# dc26_maneki-neko_badge_standalone_201807.net
KiCad netlist of a schematic drawn in EAGLE
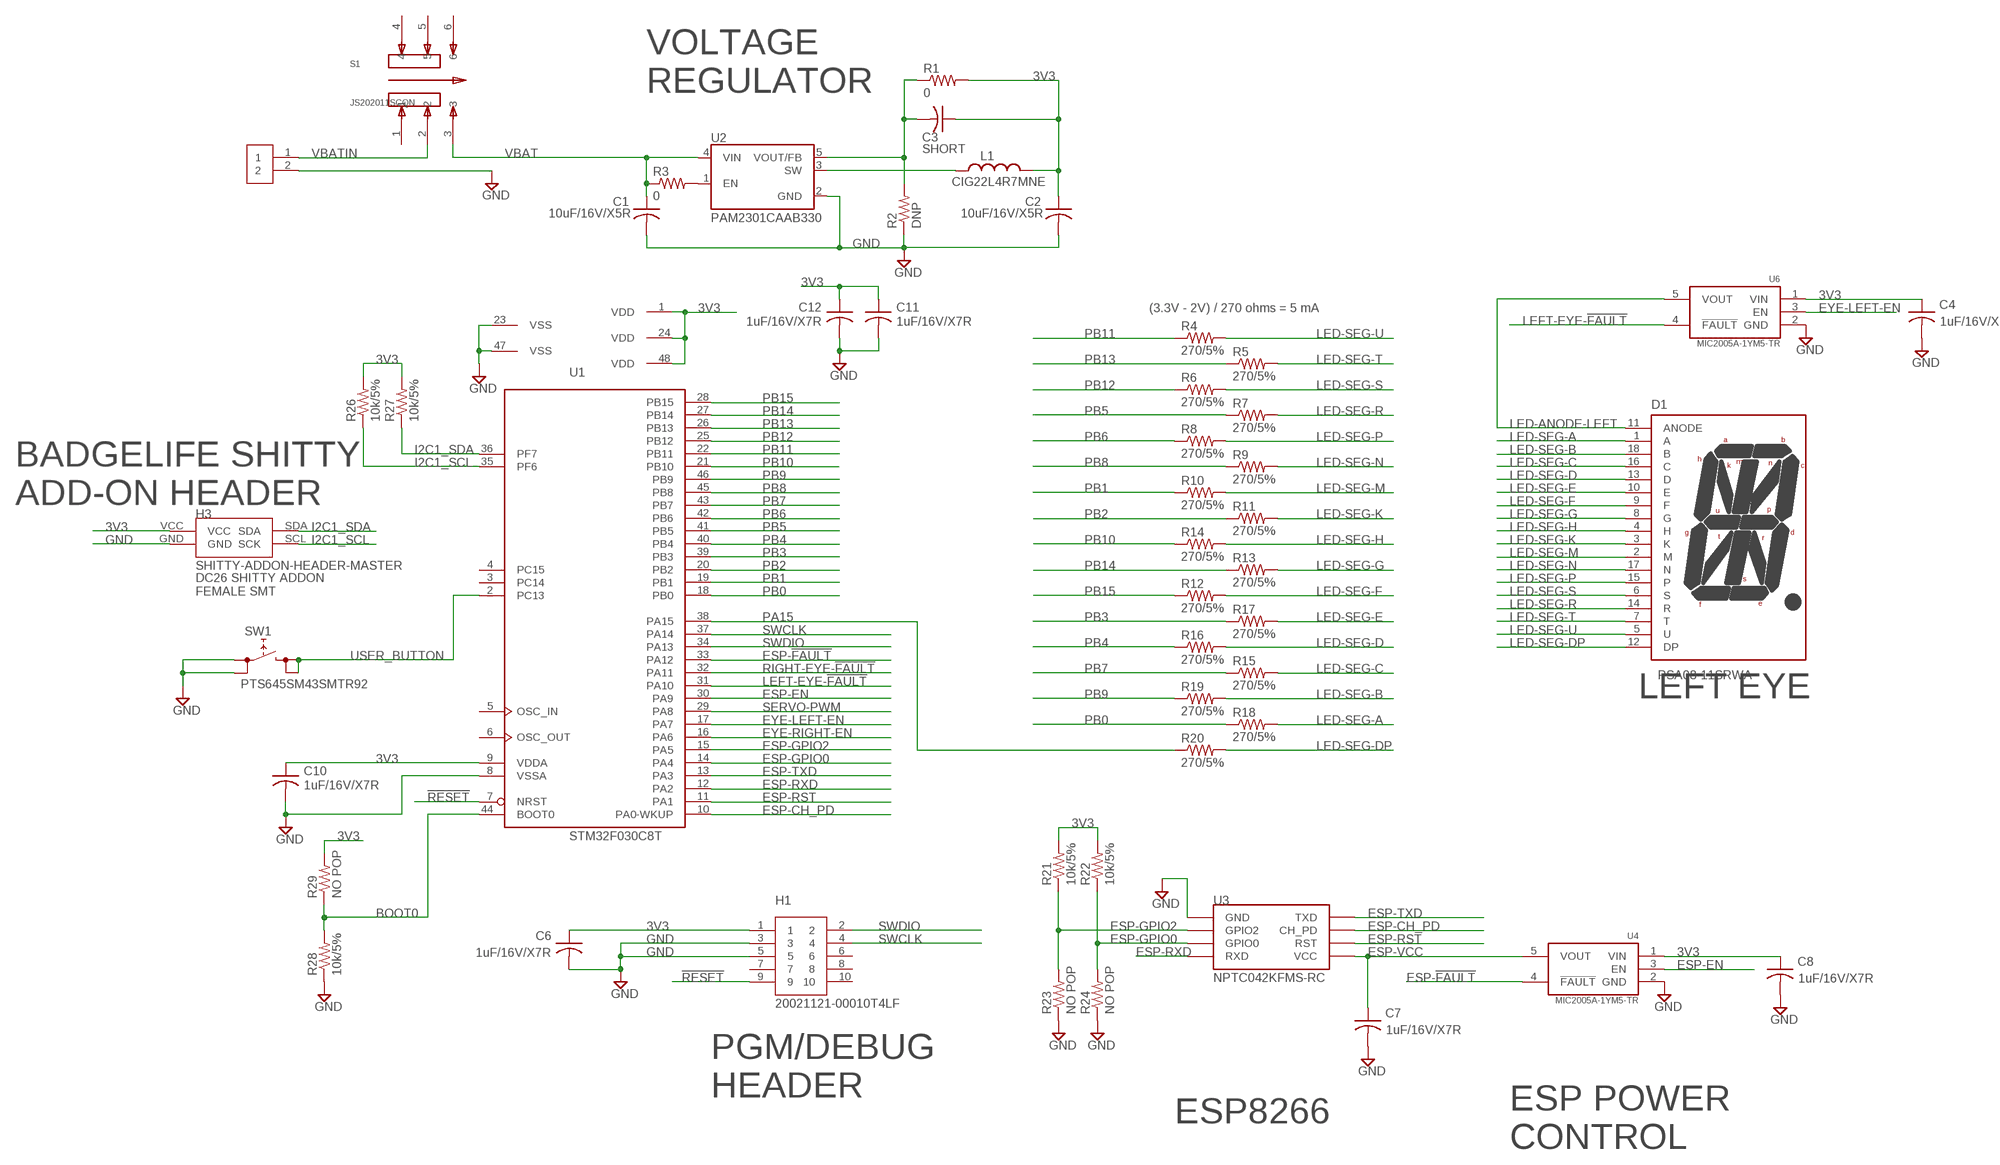
[diagram p0: schematic, sheet 1, part 1 of 2]
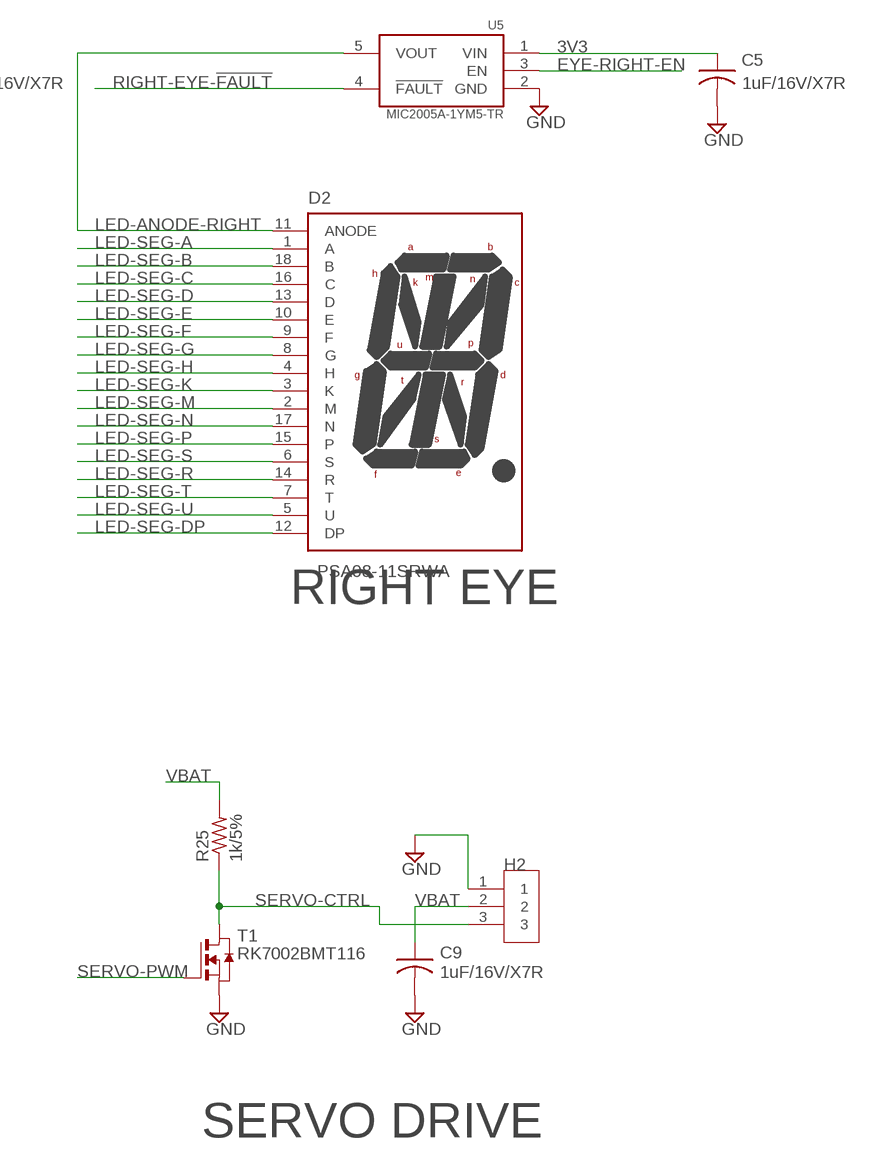
[diagram p1: schematic, sheet 1, part 2 of 2]

(export (version "E")
  (design (tool "Eeschema 10.0.6"))
  (components
    (comp (ref "C1")
      (value "10uF/16V/X5R")
      (footprint "eagle-import:C0805")
      (libsource (lib "eagle-import") (part "C-USC0805"))
    )
    (comp (ref "C2")
      (value "10uF/16V/X5R")
      (footprint "eagle-import:C0805")
      (libsource (lib "eagle-import") (part "C-USC0805"))
    )
    (comp (ref "C3")
      (value "SHORT")
      (footprint "eagle-import:C0805")
      (libsource (lib "eagle-import") (part "C-USC0805"))
    )
    (comp (ref "C4")
      (value "1uF/16V/X7R")
      (footprint "eagle-import:C0805")
      (libsource (lib "eagle-import") (part "C-USC0805"))
    )
    (comp (ref "C5")
      (value "1uF/16V/X7R")
      (footprint "eagle-import:C0805")
      (libsource (lib "eagle-import") (part "C-USC0805"))
    )
    (comp (ref "C6")
      (value "1uF/16V/X7R")
      (footprint "eagle-import:C0805")
      (libsource (lib "eagle-import") (part "C-USC0805"))
    )
    (comp (ref "C7")
      (value "1uF/16V/X7R")
      (footprint "eagle-import:C0805")
      (libsource (lib "eagle-import") (part "C-USC0805"))
    )
    (comp (ref "C8")
      (value "1uF/16V/X7R")
      (footprint "eagle-import:C0805")
      (libsource (lib "eagle-import") (part "C-USC0805"))
    )
    (comp (ref "C9")
      (value "1uF/16V/X7R")
      (footprint "eagle-import:C0805")
      (libsource (lib "eagle-import") (part "C-USC0805"))
    )
    (comp (ref "C10")
      (value "1uF/16V/X7R")
      (footprint "eagle-import:C0805")
      (libsource (lib "eagle-import") (part "C-USC0805"))
    )
    (comp (ref "C11")
      (value "1uF/16V/X7R")
      (footprint "eagle-import:C0805")
      (libsource (lib "eagle-import") (part "C-USC0805"))
    )
    (comp (ref "C12")
      (value "1uF/16V/X7R")
      (footprint "eagle-import:C0805")
      (libsource (lib "eagle-import") (part "C-USC0805"))
    )
    (comp (ref "D1")
      (value "PSA08-11SRWA")
      (footprint "eagle-import:PSA08-11SRWA")
      (libsource (lib "eagle-import") (part "PSA08-11SRWA"))
    )
    (comp (ref "D2")
      (value "PSA08-11SRWA")
      (footprint "eagle-import:PSA08-11SRWA")
      (libsource (lib "eagle-import") (part "PSA08-11SRWA"))
    )
    (comp (ref "H1")
      (value "20021121-00010T4LF")
      (footprint "eagle-import:20021121-00010T4LF")
      (libsource (lib "eagle-import") (part "20021121-00010T4LF"))
    )
    (comp (ref "H2")
      (value "M20-8890345R")
      (footprint "eagle-import:M20-8890345R")
      (libsource (lib "eagle-import") (part "M20-8890345R"))
    )
    (comp (ref "H3")
      (value "SHITTY-ADDON-HEADER-MASTER")
      (footprint "eagle-import:2X2-0.1INCH-FEMALE-SMT")
      (libsource (lib "eagle-import") (part "SHITTY-ADDON-HEADER-MASTER"))
    )
    (comp (ref "L1")
      (value "CIG22L4R7MNE")
      (footprint "eagle-import:L-1008-US")
      (libsource (lib "eagle-import") (part "CIG22L4R7MNE"))
    )
    (comp (ref "R1")
      (value "0")
      (footprint "eagle-import:R0805")
      (libsource (lib "eagle-import") (part "R-US_R0805"))
    )
    (comp (ref "R2")
      (value "DNP")
      (footprint "eagle-import:R0805")
      (libsource (lib "eagle-import") (part "R-US_R0805"))
    )
    (comp (ref "R3")
      (value "0")
      (footprint "eagle-import:R0805")
      (libsource (lib "eagle-import") (part "R-US_R0805"))
    )
    (comp (ref "R4")
      (value "270/5%")
      (footprint "eagle-import:R0805")
      (libsource (lib "eagle-import") (part "R-US_R0805"))
    )
    (comp (ref "R5")
      (value "270/5%")
      (footprint "eagle-import:R0805")
      (libsource (lib "eagle-import") (part "R-US_R0805"))
    )
    (comp (ref "R6")
      (value "270/5%")
      (footprint "eagle-import:R0805")
      (libsource (lib "eagle-import") (part "R-US_R0805"))
    )
    (comp (ref "R7")
      (value "270/5%")
      (footprint "eagle-import:R0805")
      (libsource (lib "eagle-import") (part "R-US_R0805"))
    )
    (comp (ref "R8")
      (value "270/5%")
      (footprint "eagle-import:R0805")
      (libsource (lib "eagle-import") (part "R-US_R0805"))
    )
    (comp (ref "R9")
      (value "270/5%")
      (footprint "eagle-import:R0805")
      (libsource (lib "eagle-import") (part "R-US_R0805"))
    )
    (comp (ref "R10")
      (value "270/5%")
      (footprint "eagle-import:R0805")
      (libsource (lib "eagle-import") (part "R-US_R0805"))
    )
    (comp (ref "R11")
      (value "270/5%")
      (footprint "eagle-import:R0805")
      (libsource (lib "eagle-import") (part "R-US_R0805"))
    )
    (comp (ref "R12")
      (value "270/5%")
      (footprint "eagle-import:R0805")
      (libsource (lib "eagle-import") (part "R-US_R0805"))
    )
    (comp (ref "R13")
      (value "270/5%")
      (footprint "eagle-import:R0805")
      (libsource (lib "eagle-import") (part "R-US_R0805"))
    )
    (comp (ref "R14")
      (value "270/5%")
      (footprint "eagle-import:R0805")
      (libsource (lib "eagle-import") (part "R-US_R0805"))
    )
    (comp (ref "R15")
      (value "270/5%")
      (footprint "eagle-import:R0805")
      (libsource (lib "eagle-import") (part "R-US_R0805"))
    )
    (comp (ref "R16")
      (value "270/5%")
      (footprint "eagle-import:R0805")
      (libsource (lib "eagle-import") (part "R-US_R0805"))
    )
    (comp (ref "R17")
      (value "270/5%")
      (footprint "eagle-import:R0805")
      (libsource (lib "eagle-import") (part "R-US_R0805"))
    )
    (comp (ref "R18")
      (value "270/5%")
      (footprint "eagle-import:R0805")
      (libsource (lib "eagle-import") (part "R-US_R0805"))
    )
    (comp (ref "R19")
      (value "270/5%")
      (footprint "eagle-import:R0805")
      (libsource (lib "eagle-import") (part "R-US_R0805"))
    )
    (comp (ref "R20")
      (value "270/5%")
      (footprint "eagle-import:R0805")
      (libsource (lib "eagle-import") (part "R-US_R0805"))
    )
    (comp (ref "R21")
      (value "10k/5%")
      (footprint "eagle-import:R0805")
      (libsource (lib "eagle-import") (part "R-US_R0805"))
    )
    (comp (ref "R22")
      (value "10k/5%")
      (footprint "eagle-import:R0805")
      (libsource (lib "eagle-import") (part "R-US_R0805"))
    )
    (comp (ref "R23")
      (value "NO POP")
      (footprint "eagle-import:R0805")
      (libsource (lib "eagle-import") (part "R-US_R0805"))
    )
    (comp (ref "R24")
      (value "NO POP")
      (footprint "eagle-import:R0805")
      (libsource (lib "eagle-import") (part "R-US_R0805"))
    )
    (comp (ref "R25")
      (value "1k/5%")
      (footprint "eagle-import:R0805")
      (libsource (lib "eagle-import") (part "R-US_R0805"))
    )
    (comp (ref "R26")
      (value "10k/5%")
      (footprint "eagle-import:R0805")
      (libsource (lib "eagle-import") (part "R-US_R0805"))
    )
    (comp (ref "R27")
      (value "10k/5%")
      (footprint "eagle-import:R0805")
      (libsource (lib "eagle-import") (part "R-US_R0805"))
    )
    (comp (ref "R28")
      (value "10k/5%")
      (footprint "eagle-import:R0805")
      (libsource (lib "eagle-import") (part "R-US_R0805"))
    )
    (comp (ref "R29")
      (value "NO POP")
      (footprint "eagle-import:R0805")
      (libsource (lib "eagle-import") (part "R-US_R0805"))
    )
    (comp (ref "S1")
      (value "JS202011SCQN")
      (footprint "eagle-import:SW_JS202011SCQN")
      (fields (field (name "MF") "C&K Components"))
      (libsource (lib "eagle-import") (part "JS202011SCQN"))
    )
    (comp (ref "SW1")
      (value "PTS645SM43SMTR92")
      (footprint "eagle-import:PTS645SM43SMTR92")
      (libsource (lib "eagle-import") (part "PTS645SM43SMTR92"))
    )
    (comp (ref "T1")
      (value "RK7002BMT116")
      (footprint "eagle-import:SOT-23")
      (libsource (lib "eagle-import") (part "NMOSSOT23"))
    )
    (comp (ref "U$2")
      (value "BATTPADS-SMT")
      (footprint "eagle-import:BATTPADS-SMT")
      (libsource (lib "eagle-import") (part "BATTPADS-SMT"))
    )
    (comp (ref "U1")
      (value "STM32F030C8T")
      (footprint "eagle-import:LQFP48")
      (libsource (lib "eagle-import") (part "STM32F030CT8"))
    )
    (comp (ref "U2")
      (value "PAM2301CAAB330")
      (footprint "eagle-import:SOT95P280X100-5N")
      (libsource (lib "eagle-import") (part "PAM2301CAAB330"))
    )
    (comp (ref "U3")
      (value "NPTC042KFMS-RC")
      (footprint "eagle-import:NPTC042KFMS-RC")
      (libsource (lib "eagle-import") (part "NPTC042KFMS-RC"))
    )
    (comp (ref "U4")
      (value "MIC2005A-1YM5-TR")
      (footprint "eagle-import:SOT95P270X145-5N")
      (libsource (lib "eagle-import") (part "MIC2005A-1YM5-TR"))
    )
    (comp (ref "U5")
      (value "MIC2005A-1YM5-TR")
      (footprint "eagle-import:SOT95P270X145-5N")
      (libsource (lib "eagle-import") (part "MIC2005A-1YM5-TR"))
    )
    (comp (ref "U6")
      (value "MIC2005A-1YM5-TR")
      (footprint "eagle-import:SOT95P270X145-5N")
      (libsource (lib "eagle-import") (part "MIC2005A-1YM5-TR"))
    )
  )
  (nets
    (net (code "1") (name "/3V3") (class "Default")
      (node (ref "C10") (pin "1") (pinfunction "1_1") (pintype "passive"))
      (node (ref "C11") (pin "1") (pinfunction "1_1") (pintype "passive"))
      (node (ref "C12") (pin "1") (pinfunction "1_1") (pintype "passive"))
      (node (ref "C2") (pin "1") (pinfunction "1_1") (pintype "passive"))
      (node (ref "C3") (pin "1") (pinfunction "1_1") (pintype "passive"))
      (node (ref "C4") (pin "1") (pinfunction "1_1") (pintype "passive"))
      (node (ref "C5") (pin "1") (pinfunction "1_1") (pintype "passive"))
      (node (ref "C6") (pin "1") (pinfunction "1_1") (pintype "passive"))
      (node (ref "C8") (pin "1") (pinfunction "1_1") (pintype "passive"))
      (node (ref "H1") (pin "1") (pinfunction "1_1") (pintype "bidirectional"))
      (node (ref "H3") (pin "VCC") (pinfunction "VCC_VCC") (pintype "bidirectional"))
      (node (ref "L1") (pin "P$2") (pinfunction "2_P$2") (pintype "passive"))
      (node (ref "R1") (pin "2") (pinfunction "2_2") (pintype "passive"))
      (node (ref "R21") (pin "2") (pinfunction "2_2") (pintype "passive"))
      (node (ref "R22") (pin "2") (pinfunction "2_2") (pintype "passive"))
      (node (ref "R26") (pin "2") (pinfunction "2_2") (pintype "passive"))
      (node (ref "R27") (pin "2") (pinfunction "2_2") (pintype "passive"))
      (node (ref "R29") (pin "2") (pinfunction "2_2") (pintype "passive"))
      (node (ref "U1") (pin "1") (pinfunction "VDD_1") (pintype "power_in"))
      (node (ref "U1") (pin "24") (pinfunction "VDD_24") (pintype "power_in"))
      (node (ref "U1") (pin "48") (pinfunction "VDD_48") (pintype "power_in"))
      (node (ref "U1") (pin "9") (pinfunction "VDDA_9") (pintype "power_in"))
      (node (ref "U4") (pin "1") (pinfunction "VIN_1") (pintype "bidirectional"))
      (node (ref "U5") (pin "1") (pinfunction "VIN_1") (pintype "bidirectional"))
      (node (ref "U6") (pin "1") (pinfunction "VIN_1") (pintype "bidirectional"))
    )
    (net (code "2") (name "/BOOT0") (class "Default")
      (node (ref "R28") (pin "2") (pinfunction "2_2") (pintype "passive"))
      (node (ref "R29") (pin "1") (pinfunction "1_1") (pintype "passive"))
      (node (ref "U1") (pin "44") (pinfunction "BOOT0_44") (pintype "input"))
    )
    (net (code "3") (name "/ESP-CH_PD") (class "Default")
      (node (ref "U1") (pin "10") (pinfunction "PA0-WKUP_10") (pintype "bidirectional"))
      (node (ref "U3") (pin "3") (pinfunction "CH_PD_3") (pintype "bidirectional"))
    )
    (net (code "4") (name "/ESP-EN") (class "Default")
      (node (ref "U1") (pin "30") (pinfunction "PA9_30") (pintype "bidirectional"))
      (node (ref "U4") (pin "3") (pinfunction "EN_3") (pintype "bidirectional"))
    )
    (net (code "5") (name "/ESP-GPIO0") (class "Default")
      (node (ref "R22") (pin "1") (pinfunction "1_1") (pintype "passive"))
      (node (ref "R24") (pin "2") (pinfunction "2_2") (pintype "passive"))
      (node (ref "U1") (pin "14") (pinfunction "PA4_14") (pintype "bidirectional"))
      (node (ref "U3") (pin "6") (pinfunction "GPIO0_6") (pintype "bidirectional"))
    )
    (net (code "6") (name "/ESP-GPIO2") (class "Default")
      (node (ref "R21") (pin "1") (pinfunction "1_1") (pintype "passive"))
      (node (ref "R23") (pin "2") (pinfunction "2_2") (pintype "passive"))
      (node (ref "U1") (pin "15") (pinfunction "PA5_15") (pintype "bidirectional"))
      (node (ref "U3") (pin "4") (pinfunction "GPIO2_4") (pintype "bidirectional"))
    )
    (net (code "7") (name "/ESP-RST") (class "Default")
      (node (ref "U1") (pin "11") (pinfunction "PA1_11") (pintype "bidirectional"))
      (node (ref "U3") (pin "5") (pinfunction "RST_5") (pintype "bidirectional"))
    )
    (net (code "8") (name "/ESP-RXD") (class "Default")
      (node (ref "U1") (pin "12") (pinfunction "PA2_12") (pintype "bidirectional"))
      (node (ref "U3") (pin "8") (pinfunction "RXD_8") (pintype "bidirectional"))
    )
    (net (code "9") (name "/ESP-TXD") (class "Default")
      (node (ref "U1") (pin "13") (pinfunction "PA3_13") (pintype "bidirectional"))
      (node (ref "U3") (pin "1") (pinfunction "TXD_1") (pintype "bidirectional"))
    )
    (net (code "10") (name "/ESP-VCC") (class "Default")
      (node (ref "C7") (pin "1") (pinfunction "1_1") (pintype "passive"))
      (node (ref "U3") (pin "7") (pinfunction "VCC_7") (pintype "bidirectional"))
      (node (ref "U4") (pin "5") (pinfunction "VOUT_5") (pintype "bidirectional"))
    )
    (net (code "11") (name "/ESP-~{FAULT}") (class "Default")
      (node (ref "U1") (pin "33") (pinfunction "PA12_33") (pintype "bidirectional"))
      (node (ref "U4") (pin "4") (pinfunction "~{FAULT}_4") (pintype "bidirectional"))
    )
    (net (code "12") (name "/EYE-LEFT-EN") (class "Default")
      (node (ref "U1") (pin "17") (pinfunction "PA7_17") (pintype "bidirectional"))
      (node (ref "U6") (pin "3") (pinfunction "EN_3") (pintype "bidirectional"))
    )
    (net (code "13") (name "/EYE-RIGHT-EN") (class "Default")
      (node (ref "U1") (pin "16") (pinfunction "PA6_16") (pintype "bidirectional"))
      (node (ref "U5") (pin "3") (pinfunction "EN_3") (pintype "bidirectional"))
    )
    (net (code "14") (name "/I2C1_SCL") (class "Default")
      (node (ref "H3") (pin "SCL") (pinfunction "SCK_SCL") (pintype "bidirectional"))
      (node (ref "R26") (pin "1") (pinfunction "1_1") (pintype "passive"))
      (node (ref "U1") (pin "35") (pinfunction "PF6_35") (pintype "bidirectional"))
    )
    (net (code "15") (name "/I2C1_SDA") (class "Default")
      (node (ref "H3") (pin "SDA") (pinfunction "SDA_SDA") (pintype "bidirectional"))
      (node (ref "R27") (pin "1") (pinfunction "1_1") (pintype "passive"))
      (node (ref "U1") (pin "36") (pinfunction "PF7_36") (pintype "bidirectional"))
    )
    (net (code "16") (name "/LED-ANODE-LEFT") (class "Default")
      (node (ref "D1") (pin "11") (pinfunction "ANODE_11") (pintype "bidirectional"))
      (node (ref "U6") (pin "5") (pinfunction "VOUT_5") (pintype "bidirectional"))
    )
    (net (code "17") (name "/LED-ANODE-RIGHT") (class "Default")
      (node (ref "D2") (pin "11") (pinfunction "ANODE_11") (pintype "bidirectional"))
      (node (ref "U5") (pin "5") (pinfunction "VOUT_5") (pintype "bidirectional"))
    )
    (net (code "18") (name "/LED-SEG-A") (class "Default")
      (node (ref "D1") (pin "1") (pinfunction "A_1") (pintype "bidirectional"))
      (node (ref "D2") (pin "1") (pinfunction "A_1") (pintype "bidirectional"))
      (node (ref "R18") (pin "2") (pinfunction "2_2") (pintype "passive"))
    )
    (net (code "19") (name "/LED-SEG-B") (class "Default")
      (node (ref "D1") (pin "18") (pinfunction "B_18") (pintype "bidirectional"))
      (node (ref "D2") (pin "18") (pinfunction "B_18") (pintype "bidirectional"))
      (node (ref "R19") (pin "2") (pinfunction "2_2") (pintype "passive"))
    )
    (net (code "20") (name "/LED-SEG-C") (class "Default")
      (node (ref "D1") (pin "16") (pinfunction "C_16") (pintype "bidirectional"))
      (node (ref "D2") (pin "16") (pinfunction "C_16") (pintype "bidirectional"))
      (node (ref "R15") (pin "2") (pinfunction "2_2") (pintype "passive"))
    )
    (net (code "21") (name "/LED-SEG-D") (class "Default")
      (node (ref "D1") (pin "13") (pinfunction "D_13") (pintype "bidirectional"))
      (node (ref "D2") (pin "13") (pinfunction "D_13") (pintype "bidirectional"))
      (node (ref "R16") (pin "2") (pinfunction "2_2") (pintype "passive"))
    )
    (net (code "22") (name "/LED-SEG-DP") (class "Default")
      (node (ref "D1") (pin "12") (pinfunction "DP_12") (pintype "bidirectional"))
      (node (ref "D2") (pin "12") (pinfunction "DP_12") (pintype "bidirectional"))
      (node (ref "R20") (pin "2") (pinfunction "2_2") (pintype "passive"))
    )
    (net (code "23") (name "/LED-SEG-E") (class "Default")
      (node (ref "D1") (pin "10") (pinfunction "E_10") (pintype "bidirectional"))
      (node (ref "D2") (pin "10") (pinfunction "E_10") (pintype "bidirectional"))
      (node (ref "R17") (pin "2") (pinfunction "2_2") (pintype "passive"))
    )
    (net (code "24") (name "/LED-SEG-F") (class "Default")
      (node (ref "D1") (pin "9") (pinfunction "F_9") (pintype "bidirectional"))
      (node (ref "D2") (pin "9") (pinfunction "F_9") (pintype "bidirectional"))
      (node (ref "R12") (pin "2") (pinfunction "2_2") (pintype "passive"))
    )
    (net (code "25") (name "/LED-SEG-G") (class "Default")
      (node (ref "D1") (pin "8") (pinfunction "G_8") (pintype "bidirectional"))
      (node (ref "D2") (pin "8") (pinfunction "G_8") (pintype "bidirectional"))
      (node (ref "R13") (pin "2") (pinfunction "2_2") (pintype "passive"))
    )
    (net (code "26") (name "/LED-SEG-H") (class "Default")
      (node (ref "D1") (pin "4") (pinfunction "H_4") (pintype "bidirectional"))
      (node (ref "D2") (pin "4") (pinfunction "H_4") (pintype "bidirectional"))
      (node (ref "R14") (pin "2") (pinfunction "2_2") (pintype "passive"))
    )
    (net (code "27") (name "/LED-SEG-K") (class "Default")
      (node (ref "D1") (pin "3") (pinfunction "K_3") (pintype "bidirectional"))
      (node (ref "D2") (pin "3") (pinfunction "K_3") (pintype "bidirectional"))
      (node (ref "R11") (pin "2") (pinfunction "2_2") (pintype "passive"))
    )
    (net (code "28") (name "/LED-SEG-M") (class "Default")
      (node (ref "D1") (pin "2") (pinfunction "M_2") (pintype "bidirectional"))
      (node (ref "D2") (pin "2") (pinfunction "M_2") (pintype "bidirectional"))
      (node (ref "R10") (pin "2") (pinfunction "2_2") (pintype "passive"))
    )
    (net (code "29") (name "/LED-SEG-N") (class "Default")
      (node (ref "D1") (pin "17") (pinfunction "N_17") (pintype "bidirectional"))
      (node (ref "D2") (pin "17") (pinfunction "N_17") (pintype "bidirectional"))
      (node (ref "R9") (pin "2") (pinfunction "2_2") (pintype "passive"))
    )
    (net (code "30") (name "/LED-SEG-P") (class "Default")
      (node (ref "D1") (pin "15") (pinfunction "P_15") (pintype "bidirectional"))
      (node (ref "D2") (pin "15") (pinfunction "P_15") (pintype "bidirectional"))
      (node (ref "R8") (pin "2") (pinfunction "2_2") (pintype "passive"))
    )
    (net (code "31") (name "/LED-SEG-R") (class "Default")
      (node (ref "D1") (pin "14") (pinfunction "R_14") (pintype "bidirectional"))
      (node (ref "D2") (pin "14") (pinfunction "R_14") (pintype "bidirectional"))
      (node (ref "R7") (pin "2") (pinfunction "2_2") (pintype "passive"))
    )
    (net (code "32") (name "/LED-SEG-S") (class "Default")
      (node (ref "D1") (pin "6") (pinfunction "S_6") (pintype "bidirectional"))
      (node (ref "D2") (pin "6") (pinfunction "S_6") (pintype "bidirectional"))
      (node (ref "R6") (pin "2") (pinfunction "2_2") (pintype "passive"))
    )
    (net (code "33") (name "/LED-SEG-T") (class "Default")
      (node (ref "D1") (pin "7") (pinfunction "T_7") (pintype "bidirectional"))
      (node (ref "D2") (pin "7") (pinfunction "T_7") (pintype "bidirectional"))
      (node (ref "R5") (pin "2") (pinfunction "2_2") (pintype "passive"))
    )
    (net (code "34") (name "/LED-SEG-U") (class "Default")
      (node (ref "D1") (pin "5") (pinfunction "U_5") (pintype "bidirectional"))
      (node (ref "D2") (pin "5") (pinfunction "U_5") (pintype "bidirectional"))
      (node (ref "R4") (pin "2") (pinfunction "2_2") (pintype "passive"))
    )
    (net (code "35") (name "/LEFT-EYE-~{FAULT}") (class "Default")
      (node (ref "U1") (pin "31") (pinfunction "PA10_31") (pintype "bidirectional"))
      (node (ref "U6") (pin "4") (pinfunction "~{FAULT}_4") (pintype "bidirectional"))
    )
    (net (code "36") (name "/PA15") (class "Default")
      (node (ref "R20") (pin "1") (pinfunction "1_1") (pintype "passive"))
      (node (ref "U1") (pin "38") (pinfunction "PA15_38") (pintype "bidirectional"))
    )
    (net (code "37") (name "/PB0") (class "Default")
      (node (ref "R18") (pin "1") (pinfunction "1_1") (pintype "passive"))
      (node (ref "U1") (pin "18") (pinfunction "PB0_18") (pintype "bidirectional"))
    )
    (net (code "38") (name "/PB1") (class "Default")
      (node (ref "R10") (pin "1") (pinfunction "1_1") (pintype "passive"))
      (node (ref "U1") (pin "19") (pinfunction "PB1_19") (pintype "bidirectional"))
    )
    (net (code "39") (name "/PB2") (class "Default")
      (node (ref "R11") (pin "1") (pinfunction "1_1") (pintype "passive"))
      (node (ref "U1") (pin "20") (pinfunction "PB2_20") (pintype "bidirectional"))
    )
    (net (code "40") (name "/PB3") (class "Default")
      (node (ref "R17") (pin "1") (pinfunction "1_1") (pintype "passive"))
      (node (ref "U1") (pin "39") (pinfunction "PB3_39") (pintype "bidirectional"))
    )
    (net (code "41") (name "/PB4") (class "Default")
      (node (ref "R16") (pin "1") (pinfunction "1_1") (pintype "passive"))
      (node (ref "U1") (pin "40") (pinfunction "PB4_40") (pintype "bidirectional"))
    )
    (net (code "42") (name "/PB5") (class "Default")
      (node (ref "R7") (pin "1") (pinfunction "1_1") (pintype "passive"))
      (node (ref "U1") (pin "41") (pinfunction "PB5_41") (pintype "bidirectional"))
    )
    (net (code "43") (name "/PB6") (class "Default")
      (node (ref "R8") (pin "1") (pinfunction "1_1") (pintype "passive"))
      (node (ref "U1") (pin "42") (pinfunction "PB6_42") (pintype "bidirectional"))
    )
    (net (code "44") (name "/PB7") (class "Default")
      (node (ref "R15") (pin "1") (pinfunction "1_1") (pintype "passive"))
      (node (ref "U1") (pin "43") (pinfunction "PB7_43") (pintype "bidirectional"))
    )
    (net (code "45") (name "/PB8") (class "Default")
      (node (ref "R9") (pin "1") (pinfunction "1_1") (pintype "passive"))
      (node (ref "U1") (pin "45") (pinfunction "PB8_45") (pintype "bidirectional"))
    )
    (net (code "46") (name "/PB9") (class "Default")
      (node (ref "R19") (pin "1") (pinfunction "1_1") (pintype "passive"))
      (node (ref "U1") (pin "46") (pinfunction "PB9_46") (pintype "bidirectional"))
    )
    (net (code "47") (name "/PB10") (class "Default")
      (node (ref "R14") (pin "1") (pinfunction "1_1") (pintype "passive"))
      (node (ref "U1") (pin "21") (pinfunction "PB10_21") (pintype "bidirectional"))
    )
    (net (code "48") (name "/PB11") (class "Default")
      (node (ref "R4") (pin "1") (pinfunction "1_1") (pintype "passive"))
      (node (ref "U1") (pin "22") (pinfunction "PB11_22") (pintype "bidirectional"))
    )
    (net (code "49") (name "/PB12") (class "Default")
      (node (ref "R6") (pin "1") (pinfunction "1_1") (pintype "passive"))
      (node (ref "U1") (pin "25") (pinfunction "PB12_25") (pintype "bidirectional"))
    )
    (net (code "50") (name "/PB13") (class "Default")
      (node (ref "R5") (pin "1") (pinfunction "1_1") (pintype "passive"))
      (node (ref "U1") (pin "26") (pinfunction "PB13_26") (pintype "bidirectional"))
    )
    (net (code "51") (name "/PB14") (class "Default")
      (node (ref "R13") (pin "1") (pinfunction "1_1") (pintype "passive"))
      (node (ref "U1") (pin "27") (pinfunction "PB14_27") (pintype "bidirectional"))
    )
    (net (code "52") (name "/PB15") (class "Default")
      (node (ref "R12") (pin "1") (pinfunction "1_1") (pintype "passive"))
      (node (ref "U1") (pin "28") (pinfunction "PB15_28") (pintype "bidirectional"))
    )
    (net (code "53") (name "/RIGHT-EYE-~{FAULT}") (class "Default")
      (node (ref "U1") (pin "32") (pinfunction "PA11_32") (pintype "bidirectional"))
      (node (ref "U5") (pin "4") (pinfunction "~{FAULT}_4") (pintype "bidirectional"))
    )
    (net (code "54") (name "/SERVO-CTRL") (class "Default")
      (node (ref "H2") (pin "3") (pinfunction "3_3") (pintype "bidirectional"))
      (node (ref "R25") (pin "1") (pinfunction "1_1") (pintype "passive"))
      (node (ref "T1") (pin "1") (pinfunction "D_1") (pintype "passive"))
    )
    (net (code "55") (name "/SERVO-PWM") (class "Default")
      (node (ref "T1") (pin "3") (pinfunction "G_3") (pintype "passive"))
      (node (ref "U1") (pin "29") (pinfunction "PA8_29") (pintype "bidirectional"))
    )
    (net (code "56") (name "/SWCLK") (class "Default")
      (node (ref "H1") (pin "4") (pinfunction "4_4") (pintype "bidirectional"))
      (node (ref "U1") (pin "37") (pinfunction "PA14_37") (pintype "bidirectional"))
    )
    (net (code "57") (name "/SWDIO") (class "Default")
      (node (ref "H1") (pin "2") (pinfunction "2_2") (pintype "bidirectional"))
      (node (ref "U1") (pin "34") (pinfunction "PA13_34") (pintype "bidirectional"))
    )
    (net (code "58") (name "/USER_BUTTON") (class "Default")
      (node (ref "SW1") (pin "3") (pinfunction "1_3") (pintype "passive"))
      (node (ref "SW1") (pin "4") (pinfunction "1_4") (pintype "passive"))
      (node (ref "U1") (pin "2") (pinfunction "PC13_2") (pintype "bidirectional"))
    )
    (net (code "59") (name "/VBAT") (class "Default")
      (node (ref "C1") (pin "1") (pinfunction "1_1") (pintype "passive"))
      (node (ref "C9") (pin "1") (pinfunction "1_1") (pintype "passive"))
      (node (ref "H2") (pin "2") (pinfunction "2_2") (pintype "bidirectional"))
      (node (ref "R25") (pin "2") (pinfunction "2_2") (pintype "passive"))
      (node (ref "R3") (pin "1") (pinfunction "1_1") (pintype "passive"))
      (node (ref "S1") (pin "3") (pinfunction "3_3") (pintype "passive"))
      (node (ref "U2") (pin "4") (pinfunction "VIN_4") (pintype "input"))
    )
    (net (code "60") (name "/VBATIN") (class "Default")
      (node (ref "S1") (pin "2") (pinfunction "2_2") (pintype "passive"))
      (node (ref "U$2") (pin "1") (pinfunction "1_1") (pintype "bidirectional"))
    )
    (net (code "61") (name "/~{RESET}") (class "Default")
      (node (ref "H1") (pin "9") (pinfunction "9_9") (pintype "bidirectional"))
      (node (ref "U1") (pin "7") (pinfunction "NRST_7") (pintype "bidirectional"))
    )
    (net (code "62") (name "GND") (class "Default")
      (node (ref "C1") (pin "2") (pinfunction "2_2") (pintype "passive"))
      (node (ref "C10") (pin "2") (pinfunction "2_2") (pintype "passive"))
      (node (ref "C11") (pin "2") (pinfunction "2_2") (pintype "passive"))
      (node (ref "C12") (pin "2") (pinfunction "2_2") (pintype "passive"))
      (node (ref "C2") (pin "2") (pinfunction "2_2") (pintype "passive"))
      (node (ref "C4") (pin "2") (pinfunction "2_2") (pintype "passive"))
      (node (ref "C5") (pin "2") (pinfunction "2_2") (pintype "passive"))
      (node (ref "C6") (pin "2") (pinfunction "2_2") (pintype "passive"))
      (node (ref "C7") (pin "2") (pinfunction "2_2") (pintype "passive"))
      (node (ref "C8") (pin "2") (pinfunction "2_2") (pintype "passive"))
      (node (ref "C9") (pin "2") (pinfunction "2_2") (pintype "passive"))
      (node (ref "H1") (pin "3") (pinfunction "3_3") (pintype "bidirectional"))
      (node (ref "H1") (pin "5") (pinfunction "5_5") (pintype "bidirectional"))
      (node (ref "H2") (pin "1") (pinfunction "1_1") (pintype "bidirectional"))
      (node (ref "H3") (pin "GND") (pinfunction "GND_GND") (pintype "bidirectional"))
      (node (ref "R2") (pin "1") (pinfunction "1_1") (pintype "passive"))
      (node (ref "R23") (pin "1") (pinfunction "1_1") (pintype "passive"))
      (node (ref "R24") (pin "1") (pinfunction "1_1") (pintype "passive"))
      (node (ref "R28") (pin "1") (pinfunction "1_1") (pintype "passive"))
      (node (ref "SW1") (pin "1") (pinfunction "0_1") (pintype "passive"))
      (node (ref "SW1") (pin "2") (pinfunction "0_2") (pintype "passive"))
      (node (ref "T1") (pin "2") (pinfunction "S_2") (pintype "passive"))
      (node (ref "U$2") (pin "2") (pinfunction "2_2") (pintype "bidirectional"))
      (node (ref "U1") (pin "23") (pinfunction "VSS_23") (pintype "power_in"))
      (node (ref "U1") (pin "47") (pinfunction "VSS_47") (pintype "power_in"))
      (node (ref "U1") (pin "8") (pinfunction "VSSA_8") (pintype "power_in"))
      (node (ref "U2") (pin "2") (pinfunction "GND_2") (pintype "power_in"))
      (node (ref "U3") (pin "2") (pinfunction "GND_2") (pintype "bidirectional"))
      (node (ref "U4") (pin "2") (pinfunction "GND_2") (pintype "bidirectional"))
      (node (ref "U5") (pin "2") (pinfunction "GND_2") (pintype "bidirectional"))
      (node (ref "U6") (pin "2") (pinfunction "GND_2") (pintype "bidirectional"))
    )
    (net (code "63") (name "Net-(L1-1)") (class "Default")
      (node (ref "L1") (pin "P$1") (pinfunction "1_P$1") (pintype "passive"))
      (node (ref "U2") (pin "3") (pinfunction "SW_3") (pintype "output"))
    )
    (net (code "64") (name "Net-(U2-EN)") (class "Default")
      (node (ref "R3") (pin "2") (pinfunction "2_2") (pintype "passive"))
      (node (ref "U2") (pin "1") (pinfunction "EN_1") (pintype "input"))
    )
    (net (code "65") (name "Net-(U2-VOUT{slash}FB)") (class "Default")
      (node (ref "C3") (pin "2") (pinfunction "2_2") (pintype "passive"))
      (node (ref "R1") (pin "1") (pinfunction "1_1") (pintype "passive"))
      (node (ref "R2") (pin "2") (pinfunction "2_2") (pintype "passive"))
      (node (ref "U2") (pin "5") (pinfunction "VOUT/FB_5") (pintype "output"))
    )
    (net (code "66") (name "unconnected-(H1-Pad6)") (class "Default")
      (node (ref "H1") (pin "6") (pinfunction "6_6") (pintype "bidirectional"))
    )
    (net (code "67") (name "unconnected-(H1-Pad7)") (class "Default")
      (node (ref "H1") (pin "7") (pinfunction "7_7") (pintype "bidirectional"))
    )
    (net (code "68") (name "unconnected-(H1-Pad8)") (class "Default")
      (node (ref "H1") (pin "8") (pinfunction "8_8") (pintype "bidirectional"))
    )
    (net (code "69") (name "unconnected-(H1-Pad10)") (class "Default")
      (node (ref "H1") (pin "10") (pinfunction "10_10") (pintype "bidirectional"))
    )
    (net (code "70") (name "unconnected-(S1-Pad1)") (class "Default")
      (node (ref "S1") (pin "1") (pinfunction "1_1") (pintype "passive"))
    )
    (net (code "71") (name "unconnected-(S1-Pad4)") (class "Default")
      (node (ref "S1") (pin "4") (pinfunction "4_4") (pintype "passive"))
    )
    (net (code "72") (name "unconnected-(S1-Pad5)") (class "Default")
      (node (ref "S1") (pin "5") (pinfunction "5_5") (pintype "passive"))
    )
    (net (code "73") (name "unconnected-(S1-Pad6)") (class "Default")
      (node (ref "S1") (pin "6") (pinfunction "6_6") (pintype "passive"))
    )
    (net (code "74") (name "unconnected-(U1A-OSC_IN-Pad5)") (class "Default")
      (node (ref "U1") (pin "5") (pinfunction "OSC_IN_5") (pintype "bidirectional"))
    )
    (net (code "75") (name "unconnected-(U1A-OSC_OUT-Pad6)") (class "Default")
      (node (ref "U1") (pin "6") (pinfunction "OSC_OUT_6") (pintype "bidirectional"))
    )
    (net (code "76") (name "unconnected-(U1A-PC14-Pad3)") (class "Default")
      (node (ref "U1") (pin "3") (pinfunction "PC14_3") (pintype "bidirectional"))
    )
    (net (code "77") (name "unconnected-(U1A-PC15-Pad4)") (class "Default")
      (node (ref "U1") (pin "4") (pinfunction "PC15_4") (pintype "bidirectional"))
    )
  )
)
